# CPU.net
KiCad netlist of a schematic drawn in Altium Designer
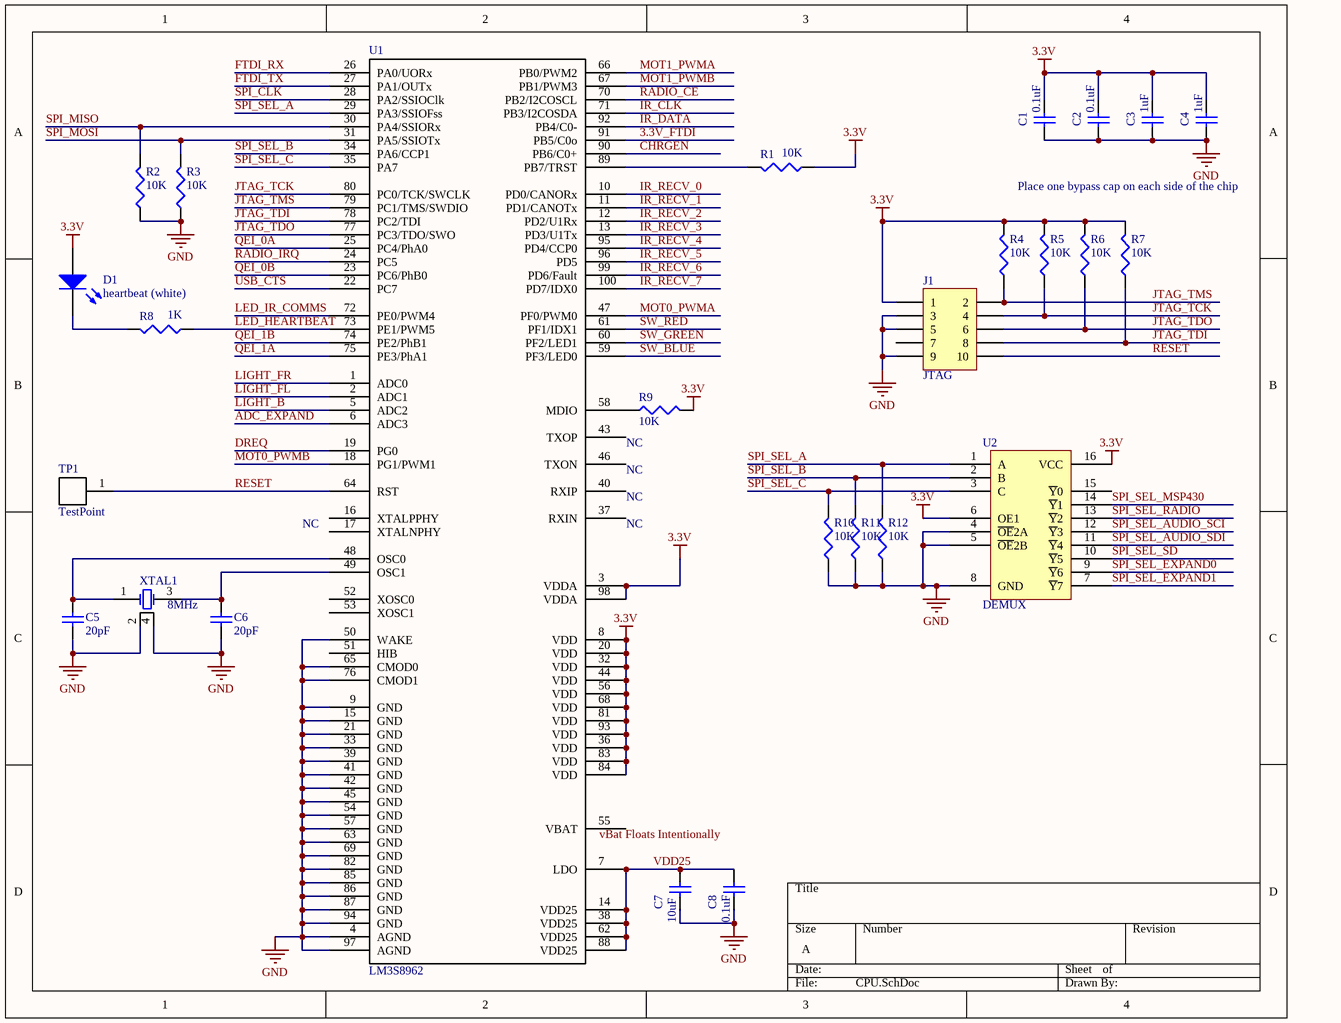
[diagram p0: CPU.SchDoc]

(export (version "E")
  (design (tool "Eeschema 10.0.6"))
  (components
    (comp (ref "C1")
      (value "0.1uF")
      (footprint "CAPC1005L")
      (description "Capacitor (Semiconductor SIM Model)")
      (fields (field (name "Comment") "Cap Semi") (field (name "PUBLISHER") "Altium Limited"))
      (libsource (lib "Miscellaneous Devices") (part "Cap Semi"))
    )
    (comp (ref "C2")
      (value "0.1uF")
      (footprint "CAPC1005L")
      (description "Capacitor (Semiconductor SIM Model)")
      (fields (field (name "Comment") "Cap Semi") (field (name "PUBLISHER") "Altium Limited"))
      (libsource (lib "Miscellaneous Devices") (part "Cap Semi"))
    )
    (comp (ref "C3")
      (value "1uF")
      (footprint "CAPC1608L")
      (description "Capacitor (Semiconductor SIM Model)")
      (fields (field (name "Comment") "Cap Semi") (field (name "PUBLISHER") "Altium Limited"))
      (libsource (lib "Miscellaneous Devices") (part "Cap Semi"))
    )
    (comp (ref "C4")
      (value "1uF")
      (footprint "CAPC1608L")
      (description "Capacitor (Semiconductor SIM Model)")
      (fields (field (name "Comment") "Cap Semi") (field (name "PUBLISHER") "Altium Limited"))
      (libsource (lib "Miscellaneous Devices") (part "Cap Semi"))
    )
    (comp (ref "C5")
      (value "20pF")
      (footprint "CAPC1005L")
      (description "Capacitor (Semiconductor SIM Model)")
      (fields (field (name "Comment") "Cap Semi") (field (name "PUBLISHER") "Altium Limited"))
      (libsource (lib "Miscellaneous Devices") (part "Cap Semi"))
    )
    (comp (ref "C6")
      (value "20pF")
      (footprint "CAPC1005L")
      (description "Capacitor (Semiconductor SIM Model)")
      (fields (field (name "Comment") "Cap Semi") (field (name "PUBLISHER") "Altium Limited"))
      (libsource (lib "Miscellaneous Devices") (part "Cap Semi"))
    )
    (comp (ref "C7")
      (value "10uF")
      (footprint "CAPC1608L")
      (description "Capacitor (Semiconductor SIM Model)")
      (fields (field (name "Comment") "Cap Semi") (field (name "PUBLISHER") "Altium Limited"))
      (libsource (lib "Miscellaneous Devices") (part "Cap Semi"))
    )
    (comp (ref "C8")
      (value "0.1uF")
      (footprint "CAPC1005L")
      (description "Capacitor (Semiconductor SIM Model)")
      (fields (field (name "Comment") "Cap Semi") (field (name "PUBLISHER") "Altium Limited"))
      (libsource (lib "Miscellaneous Devices") (part "Cap Semi"))
    )
    (comp (ref "D1")
      (value "heartbeat (white)")
      (footprint "SurfaceMount(603)")
      (libsource (lib "mrone") (part "LED"))
    )
    (comp (ref "J1")
      (value "JTAG")
      (footprint "JTAG-10")
      (description "Header, 5-Pin, Dual row, Right Angle")
      (fields (field (name "PUBLISHER") "Altium Limited"))
      (libsource (lib "Miscellaneous Connectors") (part "Header 5X2H"))
    )
    (comp (ref "R1")
      (value "10K")
      (footprint "RESC1608L")
      (description "Resistor")
      (fields (field (name "Comment") "Res3") (field (name "PUBLISHER") "Altium Limited"))
      (libsource (lib "Miscellaneous Devices") (part "Res3"))
    )
    (comp (ref "R2")
      (value "10K")
      (footprint "RESC1608L")
      (description "Resistor")
      (fields (field (name "Comment") "Res3") (field (name "PUBLISHER") "Altium Limited"))
      (libsource (lib "Miscellaneous Devices") (part "Res3"))
    )
    (comp (ref "R3")
      (value "10K")
      (footprint "RESC1608L")
      (description "Resistor")
      (fields (field (name "Comment") "Res3") (field (name "PUBLISHER") "Altium Limited"))
      (libsource (lib "Miscellaneous Devices") (part "Res3"))
    )
    (comp (ref "R4")
      (value "10K")
      (footprint "RESC1608L")
      (description "Resistor")
      (fields (field (name "Comment") "Res3") (field (name "PUBLISHER") "Altium Limited"))
      (libsource (lib "Miscellaneous Devices") (part "Res3"))
    )
    (comp (ref "R5")
      (value "10K")
      (footprint "RESC1608L")
      (description "Resistor")
      (fields (field (name "Comment") "Res3") (field (name "PUBLISHER") "Altium Limited"))
      (libsource (lib "Miscellaneous Devices") (part "Res3"))
    )
    (comp (ref "R6")
      (value "10K")
      (footprint "RESC1608L")
      (description "Resistor")
      (fields (field (name "Comment") "Res3") (field (name "PUBLISHER") "Altium Limited"))
      (libsource (lib "Miscellaneous Devices") (part "Res3"))
    )
    (comp (ref "R7")
      (value "10K")
      (footprint "RESC1608L")
      (description "Resistor")
      (fields (field (name "Comment") "Res3") (field (name "PUBLISHER") "Altium Limited"))
      (libsource (lib "Miscellaneous Devices") (part "Res3"))
    )
    (comp (ref "R8")
      (value "1K")
      (footprint "RESC1608L")
      (description "Resistor")
      (fields (field (name "Comment") "Res3") (field (name "PUBLISHER") "Altium Limited"))
      (libsource (lib "Miscellaneous Devices") (part "Res3"))
    )
    (comp (ref "R9")
      (value "10K")
      (footprint "RESC1608L")
      (description "Resistor")
      (fields (field (name "Comment") "Res3") (field (name "PUBLISHER") "Altium Limited"))
      (libsource (lib "Miscellaneous Devices") (part "Res3"))
    )
    (comp (ref "R10")
      (value "10K")
      (footprint "RESC1608L")
      (description "Resistor")
      (fields (field (name "Comment") "Res3") (field (name "PUBLISHER") "Altium Limited"))
      (libsource (lib "Miscellaneous Devices") (part "Res3"))
    )
    (comp (ref "R11")
      (value "10K")
      (footprint "RESC1608L")
      (description "Resistor")
      (fields (field (name "Comment") "Res3") (field (name "PUBLISHER") "Altium Limited"))
      (libsource (lib "Miscellaneous Devices") (part "Res3"))
    )
    (comp (ref "R12")
      (value "10K")
      (footprint "RESC1608L")
      (description "Resistor")
      (fields (field (name "Comment") "Res3") (field (name "PUBLISHER") "Altium Limited"))
      (libsource (lib "Miscellaneous Devices") (part "Res3"))
    )
    (comp (ref "TP1")
      (value "TestPoint")
      (footprint "TestPoint")
      (libsource (lib "mrone") (part "TestPoint"))
    )
    (comp (ref "U1")
      (value "LM3S8962")
      (footprint "LQFP-100")
      (libsource (lib "Schematic Components") (part "LM3S8962"))
    )
    (comp (ref "U2") (value "DEMUX") (footprint "TSSOP-16") (libsource (lib "mrone") (part "DEMUX")))
    (comp (ref "XTAL1") (value "8MHz") (footprint "CRYSTAL") (libsource (lib "mrone") (part "Crystal")))
  )
  (nets
    (net (code "1") (name "/3.3V_FTDI") (class "Default")
      (node (ref "U1") (pin "91") (pinfunction "PB5/C0o_91") (pintype "passive"))
    )
    (net (code "2") (name "/ADC_EXPAND") (class "Default")
      (node (ref "U1") (pin "6") (pinfunction "ADC3_6") (pintype "passive"))
    )
    (net (code "3") (name "/CHRGEN") (class "Default")
      (node (ref "U1") (pin "90") (pinfunction "PB6/C0+_90") (pintype "passive"))
    )
    (net (code "4") (name "/DREQ") (class "Default")
      (node (ref "U1") (pin "19") (pinfunction "PG0_19") (pintype "passive"))
    )
    (net (code "5") (name "/FTDI_RX") (class "Default")
      (node (ref "U1") (pin "26") (pinfunction "PA0/UORx_26") (pintype "passive"))
    )
    (net (code "6") (name "/FTDI_TX") (class "Default")
      (node (ref "U1") (pin "27") (pinfunction "PA1/OUTx_27") (pintype "passive"))
    )
    (net (code "7") (name "/IR_CLK") (class "Default")
      (node (ref "U1") (pin "71") (pinfunction "PB3/I2COSDA_71") (pintype "passive"))
    )
    (net (code "8") (name "/IR_DATA") (class "Default")
      (node (ref "U1") (pin "92") (pinfunction "PB4/C0-_92") (pintype "passive"))
    )
    (net (code "9") (name "/IR_RECV_0") (class "Default")
      (node (ref "U1") (pin "10") (pinfunction "PD0/CANORx_10") (pintype "passive"))
    )
    (net (code "10") (name "/IR_RECV_1") (class "Default")
      (node (ref "U1") (pin "11") (pinfunction "PD1/CANOTx_11") (pintype "passive"))
    )
    (net (code "11") (name "/IR_RECV_2") (class "Default")
      (node (ref "U1") (pin "12") (pinfunction "PD2/U1Rx_12") (pintype "passive"))
    )
    (net (code "12") (name "/IR_RECV_3") (class "Default")
      (node (ref "U1") (pin "13") (pinfunction "PD3/U1Tx_13") (pintype "passive"))
    )
    (net (code "13") (name "/IR_RECV_4") (class "Default")
      (node (ref "U1") (pin "95") (pinfunction "PD4/CCP0_95") (pintype "passive"))
    )
    (net (code "14") (name "/IR_RECV_5") (class "Default")
      (node (ref "U1") (pin "96") (pinfunction "PD5_96") (pintype "passive"))
    )
    (net (code "15") (name "/IR_RECV_6") (class "Default")
      (node (ref "U1") (pin "99") (pinfunction "PD6/Fault_99") (pintype "passive"))
    )
    (net (code "16") (name "/IR_RECV_7") (class "Default")
      (node (ref "U1") (pin "100") (pinfunction "PD7/IDX0_100") (pintype "passive"))
    )
    (net (code "17") (name "/JTAG_TCK") (class "Default")
      (node (ref "J1") (pin "4") (pinfunction "4_4") (pintype "passive"))
      (node (ref "R5") (pin "1") (pinfunction "1_1") (pintype "passive"))
      (node (ref "U1") (pin "80") (pinfunction "PC0/TCK/SWCLK_80") (pintype "passive"))
    )
    (net (code "18") (name "/JTAG_TDI") (class "Default")
      (node (ref "J1") (pin "8") (pinfunction "8_8") (pintype "passive"))
      (node (ref "R7") (pin "1") (pinfunction "1_1") (pintype "passive"))
      (node (ref "U1") (pin "78") (pinfunction "PC2/TDI_78") (pintype "passive"))
    )
    (net (code "19") (name "/JTAG_TDO") (class "Default")
      (node (ref "J1") (pin "6") (pinfunction "6_6") (pintype "passive"))
      (node (ref "R6") (pin "1") (pinfunction "1_1") (pintype "passive"))
      (node (ref "U1") (pin "77") (pinfunction "PC3/TDO/SWO_77") (pintype "passive"))
    )
    (net (code "20") (name "/JTAG_TMS") (class "Default")
      (node (ref "J1") (pin "2") (pinfunction "2_2") (pintype "passive"))
      (node (ref "R4") (pin "1") (pinfunction "1_1") (pintype "passive"))
      (node (ref "U1") (pin "79") (pinfunction "PC1/TMS/SWDIO_79") (pintype "passive"))
    )
    (net (code "21") (name "/LED_HEARTBEAT") (class "Default")
      (node (ref "R8") (pin "1") (pinfunction "1_1") (pintype "passive"))
      (node (ref "U1") (pin "73") (pinfunction "PE1/PWM5_73") (pintype "passive"))
    )
    (net (code "22") (name "/LED_IR_COMMS") (class "Default")
      (node (ref "U1") (pin "72") (pinfunction "PE0/PWM4_72") (pintype "passive"))
    )
    (net (code "23") (name "/LIGHT_B") (class "Default")
      (node (ref "U1") (pin "5") (pinfunction "ADC2_5") (pintype "passive"))
    )
    (net (code "24") (name "/LIGHT_FL") (class "Default")
      (node (ref "U1") (pin "2") (pinfunction "ADC1_2") (pintype "passive"))
    )
    (net (code "25") (name "/LIGHT_FR") (class "Default")
      (node (ref "U1") (pin "1") (pinfunction "ADC0_1") (pintype "passive"))
    )
    (net (code "26") (name "/MOT0_PWMA") (class "Default")
      (node (ref "U1") (pin "47") (pinfunction "PF0/PWM0_47") (pintype "passive"))
    )
    (net (code "27") (name "/MOT0_PWMB") (class "Default")
      (node (ref "U1") (pin "18") (pinfunction "PG1/PWM1_18") (pintype "passive"))
    )
    (net (code "28") (name "/MOT1_PWMA") (class "Default")
      (node (ref "U1") (pin "66") (pinfunction "PB0/PWM2_66") (pintype "passive"))
    )
    (net (code "29") (name "/MOT1_PWMB") (class "Default")
      (node (ref "U1") (pin "67") (pinfunction "PB1/PWM3_67") (pintype "passive"))
    )
    (net (code "30") (name "/QEI_0A") (class "Default")
      (node (ref "U1") (pin "25") (pinfunction "PC4/PhA0_25") (pintype "passive"))
    )
    (net (code "31") (name "/QEI_0B") (class "Default")
      (node (ref "U1") (pin "23") (pinfunction "PC6/PhB0_23") (pintype "passive"))
    )
    (net (code "32") (name "/QEI_1A") (class "Default")
      (node (ref "U1") (pin "75") (pinfunction "PE3/PhA1_75") (pintype "passive"))
    )
    (net (code "33") (name "/QEI_1B") (class "Default")
      (node (ref "U1") (pin "74") (pinfunction "PE2/PhB1_74") (pintype "passive"))
    )
    (net (code "34") (name "/RADIO_CE") (class "Default")
      (node (ref "U1") (pin "70") (pinfunction "PB2/I2COSCL_70") (pintype "passive"))
    )
    (net (code "35") (name "/RADIO_IRQ") (class "Default")
      (node (ref "U1") (pin "24") (pinfunction "PC5_24") (pintype "passive"))
    )
    (net (code "36") (name "/RESET") (class "Default")
      (node (ref "J1") (pin "10") (pinfunction "10_10") (pintype "passive"))
      (node (ref "TP1") (pin "1") (pintype "passive"))
      (node (ref "U1") (pin "64") (pinfunction "RST_64") (pintype "passive"))
    )
    (net (code "37") (name "/SPI_CLK") (class "Default")
      (node (ref "U1") (pin "28") (pinfunction "PA2/SSIOClk_28") (pintype "passive"))
    )
    (net (code "38") (name "/SPI_MISO") (class "Default")
      (node (ref "R2") (pin "2") (pinfunction "2_2") (pintype "passive"))
      (node (ref "U1") (pin "30") (pinfunction "PA4/SSIORx_30") (pintype "passive"))
    )
    (net (code "39") (name "/SPI_MOSI") (class "Default")
      (node (ref "R3") (pin "2") (pinfunction "2_2") (pintype "passive"))
      (node (ref "U1") (pin "31") (pinfunction "PA5/SSIOTx_31") (pintype "passive"))
    )
    (net (code "40") (name "/SPI_SEL_A") (class "Default")
      (node (ref "R12") (pin "2") (pinfunction "2_2") (pintype "passive"))
      (node (ref "U1") (pin "29") (pinfunction "PA3/SSIOFss_29") (pintype "passive"))
      (node (ref "U2") (pin "1") (pinfunction "A_1") (pintype "passive"))
    )
    (net (code "41") (name "/SPI_SEL_AUDIO_SCI") (class "Default")
      (node (ref "U2") (pin "12") (pinfunction "~{Y}3_12") (pintype "passive"))
    )
    (net (code "42") (name "/SPI_SEL_AUDIO_SDI") (class "Default")
      (node (ref "U2") (pin "11") (pinfunction "~{Y}4_11") (pintype "passive"))
    )
    (net (code "43") (name "/SPI_SEL_B") (class "Default")
      (node (ref "R11") (pin "2") (pinfunction "2_2") (pintype "passive"))
      (node (ref "U1") (pin "34") (pinfunction "PA6/CCP1_34") (pintype "passive"))
      (node (ref "U2") (pin "2") (pinfunction "B_2") (pintype "passive"))
    )
    (net (code "44") (name "/SPI_SEL_C") (class "Default")
      (node (ref "R10") (pin "2") (pinfunction "2_2") (pintype "passive"))
      (node (ref "U1") (pin "35") (pinfunction "PA7_35") (pintype "passive"))
      (node (ref "U2") (pin "3") (pinfunction "C_3") (pintype "passive"))
    )
    (net (code "45") (name "/SPI_SEL_EXPAND0") (class "Default")
      (node (ref "U2") (pin "9") (pinfunction "~{Y}6_9") (pintype "passive"))
    )
    (net (code "46") (name "/SPI_SEL_EXPAND1") (class "Default")
      (node (ref "U2") (pin "7") (pinfunction "~{Y}7_7") (pintype "passive"))
    )
    (net (code "47") (name "/SPI_SEL_MSP430") (class "Default")
      (node (ref "U2") (pin "14") (pinfunction "~{Y}1_14") (pintype "passive"))
    )
    (net (code "48") (name "/SPI_SEL_RADIO") (class "Default")
      (node (ref "U2") (pin "13") (pinfunction "~{Y}2_13") (pintype "passive"))
    )
    (net (code "49") (name "/SPI_SEL_SD") (class "Default")
      (node (ref "U2") (pin "10") (pinfunction "~{Y}5_10") (pintype "passive"))
    )
    (net (code "50") (name "/SW_BLUE") (class "Default")
      (node (ref "U1") (pin "59") (pinfunction "PF3/LED0_59") (pintype "passive"))
    )
    (net (code "51") (name "/SW_GREEN") (class "Default")
      (node (ref "U1") (pin "60") (pinfunction "PF2/LED1_60") (pintype "passive"))
    )
    (net (code "52") (name "/SW_RED") (class "Default")
      (node (ref "U1") (pin "61") (pinfunction "PF1/IDX1_61") (pintype "passive"))
    )
    (net (code "53") (name "/USB_CTS") (class "Default")
      (node (ref "U1") (pin "22") (pinfunction "PC7_22") (pintype "passive"))
    )
    (net (code "54") (name "/VDD25") (class "Default")
      (node (ref "C7") (pin "2") (pinfunction "2_2") (pintype "passive"))
      (node (ref "C8") (pin "2") (pinfunction "2_2") (pintype "passive"))
      (node (ref "U1") (pin "14") (pinfunction "VDD25_14") (pintype "passive"))
      (node (ref "U1") (pin "38") (pinfunction "VDD25_38") (pintype "passive"))
      (node (ref "U1") (pin "62") (pinfunction "VDD25_62") (pintype "passive"))
      (node (ref "U1") (pin "7") (pinfunction "LDO_7") (pintype "passive"))
      (node (ref "U1") (pin "88") (pinfunction "VDD25_88") (pintype "passive"))
    )
    (net (code "55") (name "3.3V") (class "Default")
      (node (ref "C1") (pin "2") (pinfunction "2_2") (pintype "passive"))
      (node (ref "C2") (pin "2") (pinfunction "2_2") (pintype "passive"))
      (node (ref "C3") (pin "2") (pinfunction "2_2") (pintype "passive"))
      (node (ref "C4") (pin "2") (pinfunction "2_2") (pintype "passive"))
      (node (ref "D1") (pin "1") (pinfunction "A_1") (pintype "passive"))
      (node (ref "J1") (pin "1") (pinfunction "1_1") (pintype "passive"))
      (node (ref "R1") (pin "1") (pinfunction "1_1") (pintype "passive"))
      (node (ref "R4") (pin "2") (pinfunction "2_2") (pintype "passive"))
      (node (ref "R5") (pin "2") (pinfunction "2_2") (pintype "passive"))
      (node (ref "R6") (pin "2") (pinfunction "2_2") (pintype "passive"))
      (node (ref "R7") (pin "2") (pinfunction "2_2") (pintype "passive"))
      (node (ref "R9") (pin "2") (pinfunction "2_2") (pintype "passive"))
      (node (ref "U1") (pin "20") (pinfunction "VDD_20") (pintype "passive"))
      (node (ref "U1") (pin "3") (pinfunction "VDDA_3") (pintype "passive"))
      (node (ref "U1") (pin "32") (pinfunction "VDD_32") (pintype "passive"))
      (node (ref "U1") (pin "36") (pinfunction "VDD_36") (pintype "passive"))
      (node (ref "U1") (pin "44") (pinfunction "VDD_44") (pintype "passive"))
      (node (ref "U1") (pin "56") (pinfunction "VDD_56") (pintype "passive"))
      (node (ref "U1") (pin "68") (pinfunction "VDD_68") (pintype "passive"))
      (node (ref "U1") (pin "8") (pinfunction "VDD_8") (pintype "passive"))
      (node (ref "U1") (pin "81") (pinfunction "VDD_81") (pintype "passive"))
      (node (ref "U1") (pin "83") (pinfunction "VDD_83") (pintype "passive"))
      (node (ref "U1") (pin "84") (pinfunction "VDD_84") (pintype "passive"))
      (node (ref "U1") (pin "93") (pinfunction "VDD_93") (pintype "passive"))
      (node (ref "U1") (pin "98") (pinfunction "VDDA_98") (pintype "passive"))
      (node (ref "U2") (pin "16") (pinfunction "VCC_16") (pintype "passive"))
      (node (ref "U2") (pin "6") (pinfunction "OE1_6") (pintype "passive"))
    )
    (net (code "56") (name "GND") (class "Default")
      (node (ref "C1") (pin "1") (pinfunction "1_1") (pintype "passive"))
      (node (ref "C2") (pin "1") (pinfunction "1_1") (pintype "passive"))
      (node (ref "C3") (pin "1") (pinfunction "1_1") (pintype "passive"))
      (node (ref "C4") (pin "1") (pinfunction "1_1") (pintype "passive"))
      (node (ref "C5") (pin "1") (pinfunction "1_1") (pintype "passive"))
      (node (ref "C6") (pin "1") (pinfunction "1_1") (pintype "passive"))
      (node (ref "C7") (pin "1") (pinfunction "1_1") (pintype "passive"))
      (node (ref "C8") (pin "1") (pinfunction "1_1") (pintype "passive"))
      (node (ref "J1") (pin "3") (pinfunction "3_3") (pintype "passive"))
      (node (ref "J1") (pin "5") (pinfunction "5_5") (pintype "passive"))
      (node (ref "J1") (pin "9") (pinfunction "9_9") (pintype "passive"))
      (node (ref "R10") (pin "1") (pinfunction "1_1") (pintype "passive"))
      (node (ref "R11") (pin "1") (pinfunction "1_1") (pintype "passive"))
      (node (ref "R12") (pin "1") (pinfunction "1_1") (pintype "passive"))
      (node (ref "R2") (pin "1") (pinfunction "1_1") (pintype "passive"))
      (node (ref "R3") (pin "1") (pinfunction "1_1") (pintype "passive"))
      (node (ref "U1") (pin "15") (pinfunction "GND_15") (pintype "passive"))
      (node (ref "U1") (pin "21") (pinfunction "GND_21") (pintype "passive"))
      (node (ref "U1") (pin "33") (pinfunction "GND_33") (pintype "passive"))
      (node (ref "U1") (pin "39") (pinfunction "GND_39") (pintype "passive"))
      (node (ref "U1") (pin "4") (pinfunction "AGND_4") (pintype "passive"))
      (node (ref "U1") (pin "41") (pinfunction "GND_41") (pintype "passive"))
      (node (ref "U1") (pin "42") (pinfunction "GND_42") (pintype "passive"))
      (node (ref "U1") (pin "45") (pinfunction "GND_45") (pintype "passive"))
      (node (ref "U1") (pin "50") (pinfunction "WAKE_50") (pintype "passive"))
      (node (ref "U1") (pin "54") (pinfunction "GND_54") (pintype "passive"))
      (node (ref "U1") (pin "57") (pinfunction "GND_57") (pintype "passive"))
      (node (ref "U1") (pin "63") (pinfunction "GND_63") (pintype "passive"))
      (node (ref "U1") (pin "65") (pinfunction "CMOD0_65") (pintype "passive"))
      (node (ref "U1") (pin "69") (pinfunction "GND_69") (pintype "passive"))
      (node (ref "U1") (pin "76") (pinfunction "CMOD1_76") (pintype "passive"))
      (node (ref "U1") (pin "82") (pinfunction "GND_82") (pintype "passive"))
      (node (ref "U1") (pin "85") (pinfunction "GND_85") (pintype "passive"))
      (node (ref "U1") (pin "86") (pinfunction "GND_86") (pintype "passive"))
      (node (ref "U1") (pin "87") (pinfunction "GND_87") (pintype "passive"))
      (node (ref "U1") (pin "9") (pinfunction "GND_9") (pintype "passive"))
      (node (ref "U1") (pin "94") (pinfunction "GND_94") (pintype "passive"))
      (node (ref "U1") (pin "97") (pinfunction "AGND_97") (pintype "passive"))
      (node (ref "U2") (pin "4") (pinfunction "~{OE}2A_4") (pintype "passive"))
      (node (ref "U2") (pin "5") (pinfunction "~{OE}2B_5") (pintype "passive"))
      (node (ref "U2") (pin "8") (pinfunction "GND_8") (pintype "passive"))
      (node (ref "XTAL1") (pin "2") (pinfunction "GND_2") (pintype "passive"))
      (node (ref "XTAL1") (pin "4") (pinfunction "GND_4") (pintype "passive"))
    )
    (net (code "57") (name "Net-(D1-K)") (class "Default")
      (node (ref "D1") (pin "2") (pinfunction "K_2") (pintype "passive"))
      (node (ref "R8") (pin "2") (pinfunction "2_2") (pintype "passive"))
    )
    (net (code "58") (name "Net-(U1-MDIO)") (class "Default")
      (node (ref "R9") (pin "1") (pinfunction "1_1") (pintype "passive"))
      (node (ref "U1") (pin "58") (pinfunction "MDIO_58") (pintype "passive"))
    )
    (net (code "59") (name "Net-(U1-OSC0)") (class "Default")
      (node (ref "C5") (pin "2") (pinfunction "2_2") (pintype "passive"))
      (node (ref "U1") (pin "48") (pinfunction "OSC0_48") (pintype "passive"))
      (node (ref "XTAL1") (pin "1") (pinfunction "OSC1_1") (pintype "passive"))
    )
    (net (code "60") (name "Net-(U1-OSC1)") (class "Default")
      (node (ref "C6") (pin "2") (pinfunction "2_2") (pintype "passive"))
      (node (ref "U1") (pin "49") (pinfunction "OSC1_49") (pintype "passive"))
      (node (ref "XTAL1") (pin "3") (pinfunction "OSC2_3") (pintype "passive"))
    )
    (net (code "61") (name "Net-(U1-PB7{slash}TRST)") (class "Default")
      (node (ref "R1") (pin "2") (pinfunction "2_2") (pintype "passive"))
      (node (ref "U1") (pin "89") (pinfunction "PB7/TRST_89") (pintype "passive"))
    )
    (net (code "62") (name "unconnected-(J1-Pad7)") (class "Default")
      (node (ref "J1") (pin "7") (pinfunction "7_7") (pintype "passive"))
    )
    (net (code "63") (name "unconnected-(U1-HIB-Pad51)") (class "Default")
      (node (ref "U1") (pin "51") (pinfunction "HIB_51") (pintype "passive"))
    )
    (net (code "64") (name "unconnected-(U1-RXIN-Pad37)") (class "Default")
      (node (ref "U1") (pin "37") (pinfunction "RXIN_37") (pintype "passive"))
    )
    (net (code "65") (name "unconnected-(U1-RXIP-Pad40)") (class "Default")
      (node (ref "U1") (pin "40") (pinfunction "RXIP_40") (pintype "passive"))
    )
    (net (code "66") (name "unconnected-(U1-TXON-Pad46)") (class "Default")
      (node (ref "U1") (pin "46") (pinfunction "TXON_46") (pintype "passive"))
    )
    (net (code "67") (name "unconnected-(U1-TXOP-Pad43)") (class "Default")
      (node (ref "U1") (pin "43") (pinfunction "TXOP_43") (pintype "passive"))
    )
    (net (code "68") (name "unconnected-(U1-VBAT-Pad55)") (class "Default")
      (node (ref "U1") (pin "55") (pinfunction "VBAT_55") (pintype "passive"))
    )
    (net (code "69") (name "unconnected-(U1-XOSC0-Pad52)") (class "Default")
      (node (ref "U1") (pin "52") (pinfunction "XOSC0_52") (pintype "passive"))
    )
    (net (code "70") (name "unconnected-(U1-XOSC1-Pad53)") (class "Default")
      (node (ref "U1") (pin "53") (pinfunction "XOSC1_53") (pintype "passive"))
    )
    (net (code "71") (name "unconnected-(U1-XTALNPHY-Pad17)") (class "Default")
      (node (ref "U1") (pin "17") (pinfunction "XTALNPHY_17") (pintype "passive"))
    )
    (net (code "72") (name "unconnected-(U1-XTALPPHY-Pad16)") (class "Default")
      (node (ref "U1") (pin "16") (pinfunction "XTALPPHY_16") (pintype "passive"))
    )
    (net (code "73") (name "unconnected-(U2-~{Y}0-Pad15)") (class "Default")
      (node (ref "U2") (pin "15") (pinfunction "~{Y}0_15") (pintype "passive"))
    )
  )
)
